# RH002_1.net
KiCad netlist of a schematic drawn in EAGLE
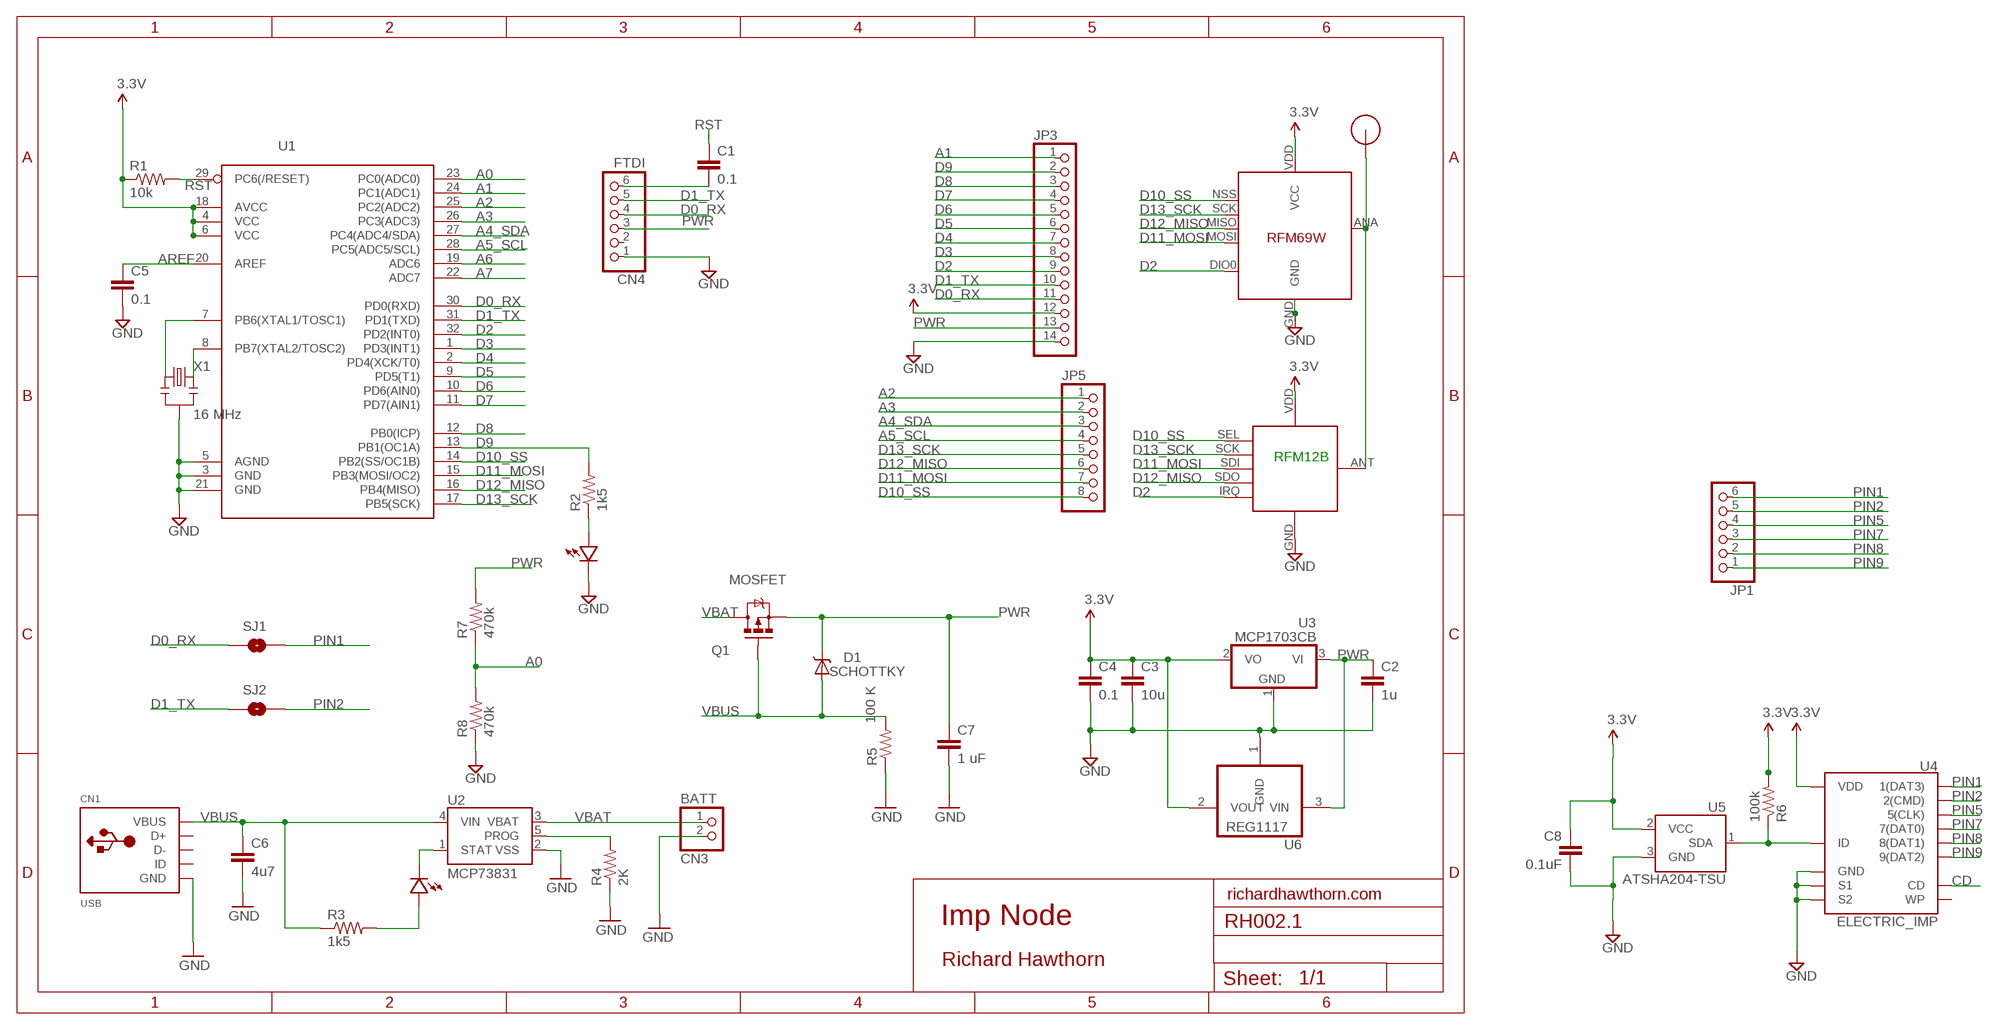
[diagram p0: schematic, sheet 1]

(export (version "E")
  (design (tool "Eeschema 10.0.6"))
  (components
    (comp (ref "C1")
      (value "0.1")
      (footprint "eagle-import:0603-CAP")
      (libsource (lib "eagle-import") (part "CAP0603-CAP"))
    )
    (comp (ref "C2")
      (value "1u")
      (footprint "eagle-import:0603-CAP")
      (libsource (lib "eagle-import") (part "CAP0603-CAP"))
    )
    (comp (ref "C3")
      (value "10u")
      (footprint "eagle-import:0805-CAP")
      (libsource (lib "eagle-import") (part "CAP0805-CAP"))
    )
    (comp (ref "C4")
      (value "0.1")
      (footprint "eagle-import:0603-CAP")
      (libsource (lib "eagle-import") (part "CAP0603-CAP"))
    )
    (comp (ref "C5")
      (value "0.1")
      (footprint "eagle-import:0603-CAP")
      (libsource (lib "eagle-import") (part "CAP0603-CAP"))
    )
    (comp (ref "C6")
      (value "4u7")
      (footprint "eagle-import:0603-CAP")
      (libsource (lib "eagle-import") (part "SparkFun_CAP0603-CAP"))
    )
    (comp (ref "C7")
      (value "1 uF")
      (footprint "eagle-import:0805")
      (libsource (lib "eagle-import") (part "SparkFun-Capacitors_CAP0805"))
    )
    (comp (ref "C8")
      (value "0.1uF")
      (footprint "eagle-import:0805")
      (libsource (lib "eagle-import") (part "SparkFun-Passives_CAP0805"))
    )
    (comp (ref "CN1")
      (value "USB")
      (footprint "eagle-import:USB-MINIB")
      (libsource (lib "eagle-import") (part "USBMINIB"))
    )
    (comp (ref "CN3")
      (value "BATT")
      (footprint "eagle-import:JST-PH-2-SMT-RA")
      (libsource (lib "eagle-import") (part "JST_2PIN-SMT-RA"))
    )
    (comp (ref "CN4")
      (value "FTDI")
      (footprint "eagle-import:1X06")
      (libsource (lib "eagle-import") (part "PINHD-1X6"))
    )
    (comp (ref "D1")
      (value "SCHOTTKY")
      (footprint "eagle-import:SMA-DIODE")
      (libsource (lib "eagle-import") (part "DIODE-SCHOTTKY_"))
    )
    (comp (ref "JP1")
      (value "PINHD-1X6")
      (footprint "eagle-import:1X06")
      (libsource (lib "eagle-import") (part "PINHD-1X6"))
    )
    (comp (ref "JP3")
      (value "PINHD-1X14")
      (footprint "eagle-import:1X14")
      (libsource (lib "eagle-import") (part "PINHD-1X14"))
    )
    (comp (ref "JP5")
      (value "PINHD-1X8")
      (footprint "eagle-import:1X08")
      (libsource (lib "eagle-import") (part "PINHD-1X8"))
    )
    (comp (ref "LED1")
      (value "LED0603")
      (footprint "eagle-import:0603-LED")
      (libsource (lib "eagle-import") (part "LED0603"))
    )
    (comp (ref "LED2")
      (value "LED0603")
      (footprint "eagle-import:0603-LED")
      (libsource (lib "eagle-import") (part "LED0603"))
    )
    (comp (ref "Q1")
      (value "MOSFET")
      (footprint "eagle-import:SOT23-3")
      (libsource (lib "eagle-import") (part "MOSFET-PCHANNELSMD"))
    )
    (comp (ref "R1")
      (value "10k")
      (footprint "eagle-import:0603-RES")
      (libsource (lib "eagle-import") (part "RESISTOR0603-RES"))
    )
    (comp (ref "R2")
      (value "1k5")
      (footprint "eagle-import:0603-RES")
      (libsource (lib "eagle-import") (part "RESISTOR0603-RES"))
    )
    (comp (ref "R3")
      (value "1k5")
      (footprint "eagle-import:0603-RES")
      (libsource (lib "eagle-import") (part "RESISTOR0603-RES"))
    )
    (comp (ref "R4")
      (value "2K")
      (footprint "eagle-import:0603-RES")
      (libsource (lib "eagle-import") (part "RESISTOR0603-RES"))
    )
    (comp (ref "R5")
      (value "100 K")
      (footprint "eagle-import:0805")
      (libsource (lib "eagle-import") (part "SparkFun-Resistors_RESISTOR0805-RES"))
    )
    (comp (ref "R6")
      (value "100k")
      (footprint "eagle-import:0805")
      (libsource (lib "eagle-import") (part "SparkFun-Passives_RESISTOR0805-RES"))
    )
    (comp (ref "R7")
      (value "470k")
      (footprint "eagle-import:0603-RES")
      (libsource (lib "eagle-import") (part "RESISTOR0603-RES"))
    )
    (comp (ref "R8")
      (value "470k")
      (footprint "eagle-import:0603-RES")
      (libsource (lib "eagle-import") (part "RESISTOR0603-RES"))
    )
    (comp (ref "RF1")
      (value "RFM12B")
      (footprint "eagle-import:RFM12B-MINPADS")
      (libsource (lib "eagle-import") (part "RFM12B_MINPADS"))
    )
    (comp (ref "RF2")
      (value "RFM69")
      (footprint "eagle-import:RFM69W-MINPADS")
      (libsource (lib "eagle-import") (part "RFM69"))
    )
    (comp (ref "SJ1")
      (value "JUMPER-PAD-2-NOYES_SILK")
      (footprint "eagle-import:PAD-JUMPER-2-NO_YES_SILK")
      (libsource (lib "eagle-import") (part "JUMPER-PAD-2-NOYES_SILK"))
    )
    (comp (ref "SJ2")
      (value "JUMPER-PAD-2-NOYES_SILK")
      (footprint "eagle-import:PAD-JUMPER-2-NO_YES_SILK")
      (libsource (lib "eagle-import") (part "JUMPER-PAD-2-NOYES_SILK"))
    )
    (comp (ref "U$1")
      (value "RFM12B_ANTENNA")
      (footprint "eagle-import:RFM12B-ANTENNA")
      (libsource (lib "eagle-import") (part "RFM12B_ANTENNA"))
    )
    (comp (ref "U1")
      (value "ATMega-328")
      (footprint "eagle-import:TQFP32-08")
      (libsource (lib "eagle-import") (part "ATMEGA168/328TQFP32"))
    )
    (comp (ref "U2")
      (value "MCP73831")
      (footprint "eagle-import:SOT23-5")
      (libsource (lib "eagle-import") (part "MCP73831"))
    )
    (comp (ref "U3")
      (value "MCP1703CB")
      (footprint "eagle-import:SOT23")
      (libsource (lib "eagle-import") (part "MCP1703CB"))
    )
    (comp (ref "U4")
      (value "ELECTRIC_IMP")
      (footprint "eagle-import:SD_MMC_SOCKET")
      (libsource (lib "eagle-import") (part "ELECTRIC_IMP"))
    )
    (comp (ref "U5")
      (value "ATSHA204-TSU")
      (footprint "eagle-import:SOT23-3")
      (libsource (lib "eagle-import") (part "ATSHA204-TSU"))
    )
    (comp (ref "U6")
      (value "REG1117")
      (footprint "eagle-import:SOT223")
      (libsource (lib "eagle-import") (part "REG1117"))
    )
    (comp (ref "X1")
      (value "16 MHz")
      (footprint "eagle-import:RESONATOR-SMD")
      (libsource (lib "eagle-import") (part "RESONATORSMD"))
    )
  )
  (nets
    (net (code "1") (name "/A0") (class "Default")
      (node (ref "R7") (pin "1") (pinfunction "1_1") (pintype "passive"))
      (node (ref "R8") (pin "2") (pinfunction "2_2") (pintype "passive"))
      (node (ref "U1") (pin "23") (pinfunction "PC0(ADC0)_23") (pintype "bidirectional"))
    )
    (net (code "2") (name "/A1") (class "Default")
      (node (ref "JP3") (pin "1") (pinfunction "1_1") (pintype "passive"))
      (node (ref "U1") (pin "24") (pinfunction "PC1(ADC1)_24") (pintype "bidirectional"))
    )
    (net (code "3") (name "/A2") (class "Default")
      (node (ref "JP5") (pin "1") (pinfunction "1_1") (pintype "passive"))
      (node (ref "U1") (pin "25") (pinfunction "PC2(ADC2)_25") (pintype "bidirectional"))
    )
    (net (code "4") (name "/A3") (class "Default")
      (node (ref "JP5") (pin "2") (pinfunction "2_2") (pintype "passive"))
      (node (ref "U1") (pin "26") (pinfunction "PC3(ADC3)_26") (pintype "bidirectional"))
    )
    (net (code "5") (name "/A4_SDA") (class "Default")
      (node (ref "JP5") (pin "3") (pinfunction "3_3") (pintype "passive"))
      (node (ref "U1") (pin "27") (pinfunction "PC4(ADC4/SDA)_27") (pintype "bidirectional"))
    )
    (net (code "6") (name "/A5_SCL") (class "Default")
      (node (ref "JP5") (pin "4") (pinfunction "4_4") (pintype "passive"))
      (node (ref "U1") (pin "28") (pinfunction "PC5(ADC5/SCL)_28") (pintype "bidirectional"))
    )
    (net (code "7") (name "/A6") (class "Default")
      (node (ref "U1") (pin "19") (pinfunction "ADC6_19") (pintype "bidirectional"))
    )
    (net (code "8") (name "/A7") (class "Default")
      (node (ref "U1") (pin "22") (pinfunction "ADC7_22") (pintype "bidirectional"))
    )
    (net (code "9") (name "/AREF") (class "Default")
      (node (ref "C5") (pin "1") (pinfunction "1_1") (pintype "passive"))
      (node (ref "U1") (pin "20") (pinfunction "AREF_20") (pintype "bidirectional"))
    )
    (net (code "10") (name "/CD") (class "Default")
      (node (ref "U4") (pin "CD") (pinfunction "CD_CD") (pintype "bidirectional"))
    )
    (net (code "11") (name "/D0_RX") (class "Default")
      (node (ref "CN4") (pin "4") (pinfunction "4_4") (pintype "passive"))
      (node (ref "JP3") (pin "11") (pinfunction "11_11") (pintype "passive"))
      (node (ref "SJ1") (pin "1") (pinfunction "1_1") (pintype "passive"))
      (node (ref "U1") (pin "30") (pinfunction "PD0(RXD)_30") (pintype "bidirectional"))
    )
    (net (code "12") (name "/D1_TX") (class "Default")
      (node (ref "CN4") (pin "5") (pinfunction "5_5") (pintype "passive"))
      (node (ref "JP3") (pin "10") (pinfunction "10_10") (pintype "passive"))
      (node (ref "SJ2") (pin "1") (pinfunction "1_1") (pintype "passive"))
      (node (ref "U1") (pin "31") (pinfunction "PD1(TXD)_31") (pintype "bidirectional"))
    )
    (net (code "13") (name "/D2") (class "Default")
      (node (ref "JP3") (pin "9") (pinfunction "9_9") (pintype "passive"))
      (node (ref "RF1") (pin "IRQ") (pinfunction "IRQ_IRQ") (pintype "bidirectional"))
      (node (ref "RF2") (pin "DIO0") (pinfunction "DIO0_DIO0") (pintype "open_collector"))
      (node (ref "U1") (pin "32") (pinfunction "PD2(INT0)_32") (pintype "bidirectional"))
    )
    (net (code "14") (name "/D3") (class "Default")
      (node (ref "JP3") (pin "8") (pinfunction "8_8") (pintype "passive"))
      (node (ref "U1") (pin "1") (pinfunction "PD3(INT1)_1") (pintype "bidirectional"))
    )
    (net (code "15") (name "/D4") (class "Default")
      (node (ref "JP3") (pin "7") (pinfunction "7_7") (pintype "passive"))
      (node (ref "U1") (pin "2") (pinfunction "PD4(XCK/T0)_2") (pintype "bidirectional"))
    )
    (net (code "16") (name "/D5") (class "Default")
      (node (ref "JP3") (pin "6") (pinfunction "6_6") (pintype "passive"))
      (node (ref "U1") (pin "9") (pinfunction "PD5(T1)_9") (pintype "bidirectional"))
    )
    (net (code "17") (name "/D6") (class "Default")
      (node (ref "JP3") (pin "5") (pinfunction "5_5") (pintype "passive"))
      (node (ref "U1") (pin "10") (pinfunction "PD6(AIN0)_10") (pintype "bidirectional"))
    )
    (net (code "18") (name "/D7") (class "Default")
      (node (ref "JP3") (pin "4") (pinfunction "4_4") (pintype "passive"))
      (node (ref "U1") (pin "11") (pinfunction "PD7(AIN1)_11") (pintype "bidirectional"))
    )
    (net (code "19") (name "/D8") (class "Default")
      (node (ref "JP3") (pin "3") (pinfunction "3_3") (pintype "passive"))
      (node (ref "U1") (pin "12") (pinfunction "PB0(ICP)_12") (pintype "bidirectional"))
    )
    (net (code "20") (name "/D9") (class "Default")
      (node (ref "JP3") (pin "2") (pinfunction "2_2") (pintype "passive"))
      (node (ref "R2") (pin "2") (pinfunction "2_2") (pintype "passive"))
      (node (ref "U1") (pin "13") (pinfunction "PB1(OC1A)_13") (pintype "bidirectional"))
    )
    (net (code "21") (name "/D10_SS") (class "Default")
      (node (ref "JP5") (pin "8") (pinfunction "8_8") (pintype "passive"))
      (node (ref "RF1") (pin "SEL") (pinfunction "SEL_SEL") (pintype "bidirectional"))
      (node (ref "RF2") (pin "NSS") (pinfunction "SEL_NSS") (pintype "input"))
      (node (ref "U1") (pin "14") (pinfunction "PB2(SS/OC1B)_14") (pintype "bidirectional"))
    )
    (net (code "22") (name "/D11_MOSI") (class "Default")
      (node (ref "JP5") (pin "7") (pinfunction "7_7") (pintype "passive"))
      (node (ref "RF1") (pin "SDI") (pinfunction "SDI/MOSI_SDI") (pintype "bidirectional"))
      (node (ref "RF2") (pin "MOSI") (pinfunction "MOSI_MOSI") (pintype "output"))
      (node (ref "U1") (pin "15") (pinfunction "PB3(MOSI/OC2)_15") (pintype "bidirectional"))
    )
    (net (code "23") (name "/D12_MISO") (class "Default")
      (node (ref "JP5") (pin "6") (pinfunction "6_6") (pintype "passive"))
      (node (ref "RF1") (pin "SDO") (pinfunction "SDO/MISO_SDO") (pintype "bidirectional"))
      (node (ref "RF2") (pin "MISO") (pinfunction "MISO_MISO") (pintype "input"))
      (node (ref "U1") (pin "16") (pinfunction "PB4(MISO)_16") (pintype "bidirectional"))
    )
    (net (code "24") (name "/D13_SCK") (class "Default")
      (node (ref "JP5") (pin "5") (pinfunction "5_5") (pintype "passive"))
      (node (ref "RF1") (pin "SCK") (pinfunction "SCK_SCK") (pintype "bidirectional"))
      (node (ref "RF2") (pin "SCK") (pinfunction "SCK_SCK") (pintype "input"))
      (node (ref "U1") (pin "17") (pinfunction "PB5(SCK)_17") (pintype "bidirectional"))
    )
    (net (code "25") (name "/PIN1") (class "Default")
      (node (ref "JP1") (pin "6") (pinfunction "6_6") (pintype "passive"))
      (node (ref "SJ1") (pin "2") (pinfunction "2_2") (pintype "passive"))
      (node (ref "U4") (pin "1") (pinfunction "1(DAT3)_1") (pintype "bidirectional"))
    )
    (net (code "26") (name "/PIN2") (class "Default")
      (node (ref "JP1") (pin "5") (pinfunction "5_5") (pintype "passive"))
      (node (ref "SJ2") (pin "2") (pinfunction "2_2") (pintype "passive"))
      (node (ref "U4") (pin "2") (pinfunction "2(CMD)_2") (pintype "bidirectional"))
    )
    (net (code "27") (name "/PIN5") (class "Default")
      (node (ref "JP1") (pin "4") (pinfunction "4_4") (pintype "passive"))
      (node (ref "U4") (pin "5") (pinfunction "5(CLK)_5") (pintype "bidirectional"))
    )
    (net (code "28") (name "/PIN7") (class "Default")
      (node (ref "JP1") (pin "3") (pinfunction "3_3") (pintype "passive"))
      (node (ref "U4") (pin "7") (pinfunction "7(DAT0)_7") (pintype "bidirectional"))
    )
    (net (code "29") (name "/PIN8") (class "Default")
      (node (ref "JP1") (pin "2") (pinfunction "2_2") (pintype "passive"))
      (node (ref "U4") (pin "8") (pinfunction "8(DAT1)_8") (pintype "bidirectional"))
    )
    (net (code "30") (name "/PIN9") (class "Default")
      (node (ref "JP1") (pin "1") (pinfunction "1_1") (pintype "passive"))
      (node (ref "U4") (pin "9") (pinfunction "9(DAT2)_9") (pintype "bidirectional"))
    )
    (net (code "31") (name "/PWR") (class "Default")
      (node (ref "C2") (pin "1") (pinfunction "1_1") (pintype "passive"))
      (node (ref "C7") (pin "1") (pinfunction "1_1") (pintype "passive"))
      (node (ref "CN4") (pin "3") (pinfunction "3_3") (pintype "passive"))
      (node (ref "D1") (pin "C") (pinfunction "C_C") (pintype "passive"))
      (node (ref "JP3") (pin "13") (pinfunction "13_13") (pintype "passive"))
      (node (ref "Q1") (pin "2") (pinfunction "S_2") (pintype "passive"))
      (node (ref "R7") (pin "2") (pinfunction "2_2") (pintype "passive"))
      (node (ref "U3") (pin "3") (pinfunction "VI_3") (pintype "input"))
      (node (ref "U6") (pin "3") (pinfunction "VIN_3") (pintype "input"))
    )
    (net (code "32") (name "/RST") (class "Default")
      (node (ref "C1") (pin "1") (pinfunction "1_1") (pintype "passive"))
      (node (ref "R1") (pin "2") (pinfunction "2_2") (pintype "passive"))
      (node (ref "U1") (pin "29") (pinfunction "PC6(/RESET)_29") (pintype "bidirectional"))
    )
    (net (code "33") (name "/VBAT") (class "Default")
      (node (ref "CN3") (pin "1") (pinfunction "2_1") (pintype "passive"))
      (node (ref "Q1") (pin "3") (pinfunction "D_3") (pintype "passive"))
      (node (ref "U2") (pin "3") (pinfunction "VBAT_3") (pintype "power_in"))
    )
    (net (code "34") (name "/VBUS") (class "Default")
      (node (ref "C6") (pin "1") (pinfunction "1_1") (pintype "passive"))
      (node (ref "CN1") (pin "VBUS") (pinfunction "VBUS_VBUS") (pintype "power_in"))
      (node (ref "D1") (pin "A") (pinfunction "A_A") (pintype "passive"))
      (node (ref "Q1") (pin "1") (pinfunction "G_1") (pintype "passive"))
      (node (ref "R3") (pin "1") (pinfunction "1_1") (pintype "passive"))
      (node (ref "R5") (pin "2") (pinfunction "2_2") (pintype "passive"))
      (node (ref "U2") (pin "4") (pinfunction "VIN_4") (pintype "power_in"))
    )
    (net (code "35") (name "3.3V") (class "Default")
      (node (ref "C3") (pin "1") (pinfunction "1_1") (pintype "passive"))
      (node (ref "C4") (pin "1") (pinfunction "1_1") (pintype "passive"))
      (node (ref "C8") (pin "1") (pinfunction "1_1") (pintype "passive"))
      (node (ref "JP3") (pin "12") (pinfunction "12_12") (pintype "passive"))
      (node (ref "R1") (pin "1") (pinfunction "1_1") (pintype "passive"))
      (node (ref "R6") (pin "2") (pinfunction "2_2") (pintype "passive"))
      (node (ref "RF1") (pin "VDD") (pinfunction "VDD_VDD") (pintype "bidirectional"))
      (node (ref "RF2") (pin "VDD") (pinfunction "VCC_VDD") (pintype "power_in"))
      (node (ref "U1") (pin "18") (pinfunction "AVCC_18") (pintype "bidirectional"))
      (node (ref "U1") (pin "4") (pinfunction "VCC_4") (pintype "bidirectional"))
      (node (ref "U1") (pin "6") (pinfunction "VCC_6") (pintype "bidirectional"))
      (node (ref "U3") (pin "2") (pinfunction "VO_2") (pintype "passive"))
      (node (ref "U4") (pin "4") (pinfunction "VDD_4") (pintype "bidirectional"))
      (node (ref "U5") (pin "2") (pinfunction "VCC_2") (pintype "bidirectional"))
      (node (ref "U6") (pin "2") (pinfunction "VOUT_2") (pintype "output"))
    )
    (net (code "36") (name "GND") (class "Default")
      (node (ref "C2") (pin "2") (pinfunction "2_2") (pintype "passive"))
      (node (ref "C3") (pin "2") (pinfunction "2_2") (pintype "passive"))
      (node (ref "C4") (pin "2") (pinfunction "2_2") (pintype "passive"))
      (node (ref "C5") (pin "2") (pinfunction "2_2") (pintype "passive"))
      (node (ref "C6") (pin "2") (pinfunction "2_2") (pintype "passive"))
      (node (ref "C7") (pin "2") (pinfunction "2_2") (pintype "passive"))
      (node (ref "C8") (pin "2") (pinfunction "2_2") (pintype "passive"))
      (node (ref "CN1") (pin "GND") (pinfunction "GND_GND") (pintype "power_in"))
      (node (ref "CN3") (pin "2") (pinfunction "1_2") (pintype "passive"))
      (node (ref "CN4") (pin "1") (pinfunction "1_1") (pintype "passive"))
      (node (ref "JP3") (pin "14") (pinfunction "14_14") (pintype "passive"))
      (node (ref "LED2") (pin "MINUS") (pinfunction "MINUS_MINUS") (pintype "passive"))
      (node (ref "R4") (pin "1") (pinfunction "1_1") (pintype "passive"))
      (node (ref "R5") (pin "1") (pinfunction "1_1") (pintype "passive"))
      (node (ref "R8") (pin "1") (pinfunction "1_1") (pintype "passive"))
      (node (ref "RF1") (pin "GND") (pinfunction "GND_GND") (pintype "bidirectional"))
      (node (ref "RF2") (pin "GND") (pinfunction "GND_GND") (pintype "power_in"))
      (node (ref "U1") (pin "21") (pinfunction "GND_21") (pintype "bidirectional"))
      (node (ref "U1") (pin "3") (pinfunction "GND_3") (pintype "bidirectional"))
      (node (ref "U1") (pin "5") (pinfunction "AGND_5") (pintype "bidirectional"))
      (node (ref "U2") (pin "2") (pinfunction "VSS_2") (pintype "power_in"))
      (node (ref "U3") (pin "1") (pinfunction "GND_1") (pintype "passive"))
      (node (ref "U4") (pin "3") (pinfunction "GND_3") (pintype "bidirectional"))
      (node (ref "U4") (pin "S1") (pinfunction "S1_S1") (pintype "bidirectional"))
      (node (ref "U4") (pin "S2") (pinfunction "S2_S2") (pintype "bidirectional"))
      (node (ref "U5") (pin "3") (pinfunction "GND_3") (pintype "bidirectional"))
      (node (ref "U6") (pin "1") (pinfunction "GND_1") (pintype "power_in"))
      (node (ref "X1") (pin "2") (pinfunction "2_2") (pintype "passive"))
    )
    (net (code "37") (name "Net-(C1-Pad2)") (class "Default")
      (node (ref "C1") (pin "2") (pinfunction "2_2") (pintype "passive"))
      (node (ref "CN4") (pin "6") (pinfunction "6_6") (pintype "passive"))
    )
    (net (code "38") (name "Net-(LED1-PadPLUS)") (class "Default")
      (node (ref "LED1") (pin "PLUS") (pinfunction "PLUS_PLUS") (pintype "passive"))
      (node (ref "R3") (pin "2") (pinfunction "2_2") (pintype "passive"))
    )
    (net (code "39") (name "Net-(LED2-PadPLUS)") (class "Default")
      (node (ref "LED2") (pin "PLUS") (pinfunction "PLUS_PLUS") (pintype "passive"))
      (node (ref "R2") (pin "1") (pinfunction "1_1") (pintype "passive"))
    )
    (net (code "40") (name "Net-(RF2-ANT)") (class "Default")
      (node (ref "RF1") (pin "ANT") (pinfunction "ANT_ANT") (pintype "bidirectional"))
      (node (ref "RF2") (pin "ANA") (pinfunction "ANT_ANA") (pintype "passive"))
      (node (ref "U$1") (pin "P$1") (pinfunction "1_P$1") (pintype "bidirectional"))
    )
    (net (code "41") (name "Net-(U1-PB6(XTAL1{slash}TOSC1))") (class "Default")
      (node (ref "U1") (pin "7") (pinfunction "PB6(XTAL1/TOSC1)_7") (pintype "bidirectional"))
      (node (ref "X1") (pin "1") (pinfunction "1_1") (pintype "passive"))
    )
    (net (code "42") (name "Net-(U1-PB7(XTAL2{slash}TOSC2))") (class "Default")
      (node (ref "U1") (pin "8") (pinfunction "PB7(XTAL2/TOSC2)_8") (pintype "bidirectional"))
      (node (ref "X1") (pin "3") (pinfunction "3_3") (pintype "passive"))
    )
    (net (code "43") (name "Net-(U2-PROG)") (class "Default")
      (node (ref "R4") (pin "2") (pinfunction "2_2") (pintype "passive"))
      (node (ref "U2") (pin "5") (pinfunction "PROG_5") (pintype "input"))
    )
    (net (code "44") (name "Net-(U2-STAT)") (class "Default")
      (node (ref "LED1") (pin "MINUS") (pinfunction "MINUS_MINUS") (pintype "passive"))
      (node (ref "U2") (pin "1") (pinfunction "STAT_1") (pintype "output"))
    )
    (net (code "45") (name "Net-(U4-ID)") (class "Default")
      (node (ref "R6") (pin "1") (pinfunction "1_1") (pintype "passive"))
      (node (ref "U4") (pin "6") (pinfunction "ID_6") (pintype "bidirectional"))
      (node (ref "U5") (pin "1") (pinfunction "SDA_1") (pintype "bidirectional"))
    )
    (net (code "46") (name "unconnected-(CN1-PadD+)") (class "Default")
      (node (ref "CN1") (pin "D+") (pinfunction "D+_D+") (pintype "bidirectional"))
    )
    (net (code "47") (name "unconnected-(CN1-PadD-)") (class "Default")
      (node (ref "CN1") (pin "D-") (pinfunction "D-_D-") (pintype "bidirectional"))
    )
    (net (code "48") (name "unconnected-(CN1-PadID)") (class "Default")
      (node (ref "CN1") (pin "ID") (pinfunction "ID_ID") (pintype "bidirectional"))
    )
    (net (code "49") (name "unconnected-(CN4-Pad2)") (class "Default")
      (node (ref "CN4") (pin "2") (pinfunction "2_2") (pintype "passive"))
    )
    (net (code "50") (name "unconnected-(U4-PadWP)") (class "Default")
      (node (ref "U4") (pin "WP") (pinfunction "WP_WP") (pintype "bidirectional"))
    )
  )
)
